# esp_slave.net
KiCad netlist of a schematic drawn in Altium Designer
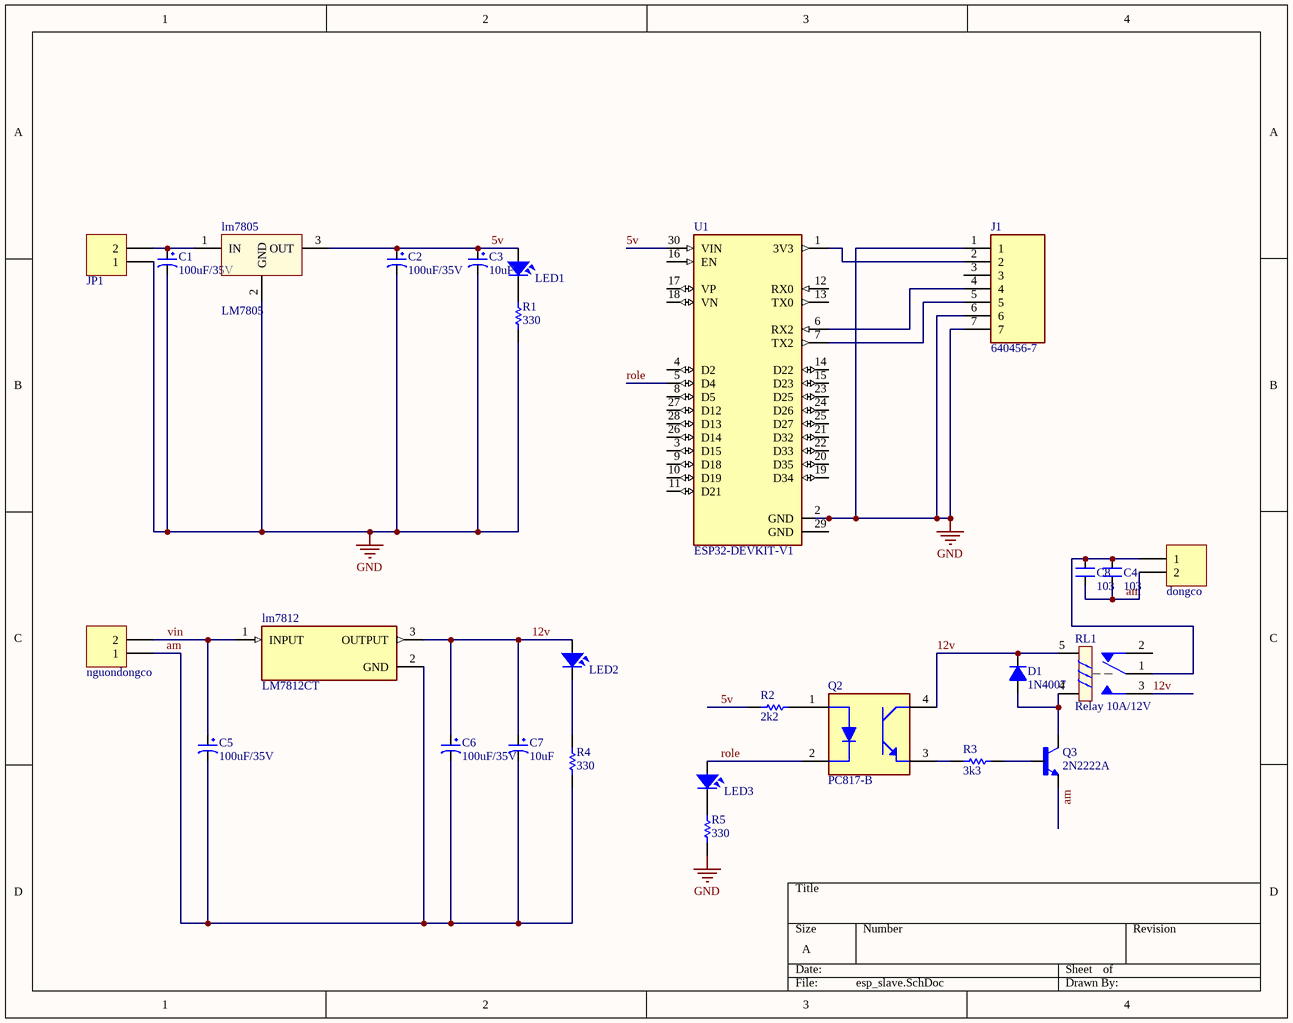
[diagram p0: esp_slave.SchDoc]

(export (version "E")
  (design (tool "Eeschema 10.0.6"))
  (components
    (comp (ref "C1")
      (value "100uF/35V")
      (footprint "CP1.5/3.4")
      (description "Cap 100uF/35V - 470uF/16V")
      (libsource (lib "syhaunguyen") (part "CP3"))
    )
    (comp (ref "C2")
      (value "100uF/35V")
      (footprint "CP1.5/3.4")
      (description "Cap 100uF/35V - 470uF/16V")
      (libsource (lib "syhaunguyen") (part "CP3"))
    )
    (comp (ref "C3")
      (value "10uF")
      (footprint "CP1/2")
      (description "Cap P  0,1uF < 22uF , 16 - 50V")
      (libsource (lib "syhaunguyen") (part "CP1"))
    )
    (comp (ref "C4")
      (value "103")
      (footprint "CN1.5")
      (description "Cap np 682pF => 104pF")
      (libsource (lib "syhaunguyen") (part "CN1.5"))
    )
    (comp (ref "C5")
      (value "100uF/35V")
      (footprint "CP1.5/3.4")
      (description "Cap 100uF/35V - 470uF/16V")
      (libsource (lib "syhaunguyen") (part "CP3"))
    )
    (comp (ref "C6")
      (value "100uF/35V")
      (footprint "CP1.5/3.4")
      (description "Cap 100uF/35V - 470uF/16V")
      (libsource (lib "syhaunguyen") (part "CP3"))
    )
    (comp (ref "C7")
      (value "10uF")
      (footprint "CP1/2")
      (description "Cap P  0,1uF < 22uF , 16 - 50V")
      (libsource (lib "syhaunguyen") (part "CP1"))
    )
    (comp (ref "C8")
      (value "103")
      (footprint "CN1.5")
      (description "Cap np 682pF => 104pF")
      (libsource (lib "syhaunguyen") (part "CN1.5"))
    )
    (comp (ref "D1")
      (value "1N4007")
      (footprint "D1A")
      (description "Diode 1A")
      (libsource (lib "syhaunguyen") (part "D1A"))
    )
    (comp (ref "dongco")
      (value "Header 2_1")
      (footprint "HED2")
      (description "Header, 2-Pin")
      (fields (field (name "MANUFACTURER") "Generic Components"))
      (libsource (lib "syhaunguyen") (part "Header 2_1"))
    )
    (comp (ref "J1")
      (value "640456-7")
      (footprint "TE_640456-7")
      (description "Header Friction Lock MTA-100 7 250 VAC Polyester Tin Copper Alloy Tin ¦ TE Connectivity 640456-7")
      (fields (field (name "MF") "TE Connectivity"))
      (libsource (lib "640456-7") (part "640456-7"))
    )
    (comp (ref "JP1")
      (value "Header 2_1")
      (footprint "HED2")
      (description "Header, 2-Pin")
      (fields (field (name "MANUFACTURER") "Generic Components"))
      (libsource (lib "") (part "Header 2_1_1"))
    )
    (comp (ref "LED1")
      (value "LED")
      (footprint "LED-3")
      (description "LED Single colour Green and Red")
      (libsource (lib "syhaunguyen") (part "LED"))
    )
    (comp (ref "LED2")
      (value "LED")
      (footprint "LED-3")
      (description "LED Single colour Green and Red")
      (libsource (lib "syhaunguyen") (part "LED"))
    )
    (comp (ref "LED3")
      (value "LED")
      (footprint "LED-3")
      (description "LED Single colour Green and Red")
      (libsource (lib "syhaunguyen") (part "LED"))
    )
    (comp (ref "lm7805")
      (value "LM7805")
      (footprint "QTO-220")
      (description "On ap +, from + 5 to + 24VDC")
      (libsource (lib "syhaunguyen") (part "LM78xx"))
    )
    (comp (ref "lm7812")
      (value "LM7812CT")
      (footprint "TO253P1057X470X2040-3")
      (description "Linear Voltage Regulator IC Positive Fixed 1 Output 1A TO-220-3")
      (fields (field (name "MF") "ON Semiconductor"))
      (libsource (lib "LM7812CT") (part "LM7812CT"))
    )
    (comp (ref "nguondongco")
      (value "Header 2_1")
      (footprint "HED2")
      (description "Header, 2-Pin")
      (fields (field (name "MANUFACTURER") "Generic Components"))
      (libsource (lib "") (part "Header 2_1_1"))
    )
    (comp (ref "Q2")
      (value "PC817-B")
      (footprint "DIP762W50P254L650H455Q4B")
      (description "Phototransistors 4-DIP (0.300, 7.62mm)")
      (fields (field (name "MF") "American Bright"))
      (libsource (lib "PC817-B") (part "PC817-B"))
    )
    (comp (ref "Q3")
      (value "2N2222A")
      (footprint "TO92254P470H750-3")
      (description "BJT, TO-92, 40V, 600mA, NPN, 0.625W, 150Â°C")
      (fields (field (name "MF") "Diotec Semiconductor"))
      (libsource (lib "2N2222A") (part "2N2222A"))
    )
    (comp (ref "R1")
      (value "330")
      (footprint "R1/4W")
      (description "Resistor")
      (fields
        (field (name "MANUFACTURER") "Generic Components")
        (field (name "Comment") "Res1")
        (field (name "PUBLISHER") "Altium Hobart Technology Centre")
      )
      (libsource (lib "syhaunguyen") (part "Res1_4"))
    )
    (comp (ref "R2")
      (value "2k2")
      (footprint "R1/4W")
      (description "Resistor")
      (fields
        (field (name "MANUFACTURER") "Generic Components")
        (field (name "Comment") "Res1")
        (field (name "PUBLISHER") "Altium Hobart Technology Centre")
      )
      (libsource (lib "syhaunguyen") (part "Res1_4"))
    )
    (comp (ref "R3")
      (value "3k3")
      (footprint "R1/4W")
      (description "Resistor")
      (fields
        (field (name "MANUFACTURER") "Generic Components")
        (field (name "Comment") "Res1")
        (field (name "PUBLISHER") "Altium Hobart Technology Centre")
      )
      (libsource (lib "syhaunguyen") (part "Res1_4"))
    )
    (comp (ref "R4")
      (value "330")
      (footprint "R1/4W")
      (description "Resistor")
      (fields
        (field (name "MANUFACTURER") "Generic Components")
        (field (name "Comment") "Res1")
        (field (name "PUBLISHER") "Altium Hobart Technology Centre")
      )
      (libsource (lib "syhaunguyen") (part "Res1_4"))
    )
    (comp (ref "R5")
      (value "330")
      (footprint "R1/4W")
      (description "Resistor")
      (fields
        (field (name "MANUFACTURER") "Generic Components")
        (field (name "Comment") "Res1")
        (field (name "PUBLISHER") "Altium Hobart Technology Centre")
      )
      (libsource (lib "syhaunguyen") (part "Res1_4"))
    )
    (comp (ref "RL1")
      (value "Relay 10A/12V")
      (footprint "RL_SPDT_10A")
      (description "Relay SPDT,10A - 12VDC 5 Pin")
      (libsource (lib "syhaunguyen") (part "Relay 1"))
    )
    (comp (ref "U1")
      (value "ESP32-DEVKIT-V1")
      (footprint "MODULE_ESP32_DEVKIT_V1")
      (fields (field (name "MF") "Do it"))
      (libsource (lib "ESP32-DEVKIT-V1") (part "ESP32-DEVKIT-V1"))
    )
  )
  (nets
    (net (code "1") (name "/5v") (class "Default")
      (node (ref "C2") (pin "1") (pinfunction "1_1") (pintype "passive"))
      (node (ref "C3") (pin "1") (pinfunction "1_1") (pintype "passive"))
      (node (ref "LED1") (pin "1") (pinfunction "1_1") (pintype "passive"))
      (node (ref "R2") (pin "1") (pinfunction "1_1") (pintype "passive"))
      (node (ref "U1") (pin "30") (pinfunction "VIN_30") (pintype "input"))
      (node (ref "lm7805") (pin "3") (pinfunction "OUT_3") (pintype "passive"))
    )
    (net (code "2") (name "/12v") (class "Default")
      (node (ref "C6") (pin "1") (pinfunction "1_1") (pintype "passive"))
      (node (ref "C7") (pin "1") (pinfunction "1_1") (pintype "passive"))
      (node (ref "D1") (pin "2") (pinfunction "K_2") (pintype "passive"))
      (node (ref "LED2") (pin "1") (pinfunction "1_1") (pintype "passive"))
      (node (ref "Q2") (pin "4") (pinfunction "COLLECTOR_4") (pintype "passive"))
      (node (ref "RL1") (pin "3") (pinfunction "3_3") (pintype "passive"))
      (node (ref "RL1") (pin "5") (pinfunction "5_5") (pintype "passive"))
      (node (ref "lm7812") (pin "3") (pinfunction "OUTPUT_3") (pintype "output"))
    )
    (net (code "3") (name "/am") (class "Default")
      (node (ref "C4") (pin "1") (pinfunction "1_1") (pintype "passive"))
      (node (ref "C5") (pin "2") (pinfunction "2_2") (pintype "passive"))
      (node (ref "C6") (pin "2") (pinfunction "2_2") (pintype "passive"))
      (node (ref "C7") (pin "2") (pinfunction "2_2") (pintype "passive"))
      (node (ref "C8") (pin "1") (pinfunction "1_1") (pintype "passive"))
      (node (ref "Q3") (pin "1") (pinfunction "E_1") (pintype "passive"))
      (node (ref "R4") (pin "2") (pinfunction "2_2") (pintype "passive"))
      (node (ref "dongco") (pin "2") (pinfunction "2_2") (pintype "passive"))
      (node (ref "lm7812") (pin "2") (pinfunction "GND_2") (pintype "power_in"))
      (node (ref "nguondongco") (pin "1") (pinfunction "1_1") (pintype "passive"))
    )
    (net (code "4") (name "/role") (class "Default")
      (node (ref "LED3") (pin "1") (pinfunction "1_1") (pintype "passive"))
      (node (ref "Q2") (pin "2") (pinfunction "CATHODE_2") (pintype "passive"))
      (node (ref "U1") (pin "5") (pinfunction "D4_5") (pintype "bidirectional"))
    )
    (net (code "5") (name "/vin") (class "Default")
      (node (ref "C5") (pin "1") (pinfunction "1_1") (pintype "passive"))
      (node (ref "lm7812") (pin "1") (pinfunction "INPUT_1") (pintype "input"))
      (node (ref "nguondongco") (pin "2") (pinfunction "2_2") (pintype "passive"))
    )
    (net (code "6") (name "GND") (class "Default")
      (node (ref "C1") (pin "2") (pinfunction "2_2") (pintype "passive"))
      (node (ref "C2") (pin "2") (pinfunction "2_2") (pintype "passive"))
      (node (ref "C3") (pin "2") (pinfunction "2_2") (pintype "passive"))
      (node (ref "J1") (pin "1") (pinfunction "1_1") (pintype "passive"))
      (node (ref "J1") (pin "6") (pinfunction "6_6") (pintype "passive"))
      (node (ref "J1") (pin "7") (pinfunction "7_7") (pintype "passive"))
      (node (ref "JP1") (pin "1") (pinfunction "1_1") (pintype "passive"))
      (node (ref "R1") (pin "2") (pinfunction "2_2") (pintype "passive"))
      (node (ref "R5") (pin "2") (pinfunction "2_2") (pintype "passive"))
      (node (ref "U1") (pin "2") (pinfunction "GND_2") (pintype "power_in"))
      (node (ref "lm7805") (pin "2") (pinfunction "GND_2") (pintype "passive"))
    )
    (net (code "7") (name "Net-(C4-Pad2)") (class "Default")
      (node (ref "C4") (pin "2") (pinfunction "2_2") (pintype "passive"))
      (node (ref "C8") (pin "2") (pinfunction "2_2") (pintype "passive"))
      (node (ref "RL1") (pin "1") (pinfunction "1_1") (pintype "passive"))
      (node (ref "dongco") (pin "1") (pinfunction "1_1") (pintype "passive"))
    )
    (net (code "8") (name "Net-(D1-A)") (class "Default")
      (node (ref "D1") (pin "1") (pinfunction "A_1") (pintype "passive"))
      (node (ref "Q3") (pin "3") (pinfunction "C_3") (pintype "passive"))
      (node (ref "RL1") (pin "4") (pinfunction "4_4") (pintype "passive"))
    )
    (net (code "9") (name "Net-(LED1-Pad2)") (class "Default")
      (node (ref "LED1") (pin "2") (pinfunction "2_2") (pintype "passive"))
      (node (ref "R1") (pin "1") (pinfunction "1_1") (pintype "passive"))
    )
    (net (code "10") (name "Net-(LED2-Pad2)") (class "Default")
      (node (ref "LED2") (pin "2") (pinfunction "2_2") (pintype "passive"))
      (node (ref "R4") (pin "1") (pinfunction "1_1") (pintype "passive"))
    )
    (net (code "11") (name "Net-(LED3-Pad2)") (class "Default")
      (node (ref "LED3") (pin "2") (pinfunction "2_2") (pintype "passive"))
      (node (ref "R5") (pin "1") (pinfunction "1_1") (pintype "passive"))
    )
    (net (code "12") (name "Net-(Q2-ANODE)") (class "Default")
      (node (ref "Q2") (pin "1") (pinfunction "ANODE_1") (pintype "passive"))
      (node (ref "R2") (pin "2") (pinfunction "2_2") (pintype "passive"))
    )
    (net (code "13") (name "Net-(Q2-EMITTER)") (class "Default")
      (node (ref "Q2") (pin "3") (pinfunction "EMITTER_3") (pintype "passive"))
      (node (ref "R3") (pin "1") (pinfunction "1_1") (pintype "passive"))
    )
    (net (code "14") (name "Net-(Q3-B)") (class "Default")
      (node (ref "Q3") (pin "2") (pinfunction "B_2") (pintype "passive"))
      (node (ref "R3") (pin "2") (pinfunction "2_2") (pintype "passive"))
    )
    (net (code "15") (name "Net-(U1-3V3)") (class "Default")
      (node (ref "J1") (pin "2") (pinfunction "2_2") (pintype "passive"))
      (node (ref "U1") (pin "1") (pinfunction "3V3_1") (pintype "output"))
    )
    (net (code "16") (name "Net-(U1-RX2)") (class "Default")
      (node (ref "J1") (pin "4") (pinfunction "4_4") (pintype "passive"))
      (node (ref "U1") (pin "6") (pinfunction "RX2_6") (pintype "input"))
    )
    (net (code "17") (name "Net-(U1-TX2)") (class "Default")
      (node (ref "J1") (pin "5") (pinfunction "5_5") (pintype "passive"))
      (node (ref "U1") (pin "7") (pinfunction "TX2_7") (pintype "output"))
    )
    (net (code "18") (name "Net-(lm7805-IN)") (class "Default")
      (node (ref "C1") (pin "1") (pinfunction "1_1") (pintype "passive"))
      (node (ref "JP1") (pin "2") (pinfunction "2_2") (pintype "passive"))
      (node (ref "lm7805") (pin "1") (pinfunction "IN_1") (pintype "passive"))
    )
    (net (code "19") (name "unconnected-(J1-Pad3)") (class "Default")
      (node (ref "J1") (pin "3") (pinfunction "3_3") (pintype "passive"))
    )
    (net (code "20") (name "unconnected-(RL1-Pad2)") (class "Default")
      (node (ref "RL1") (pin "2") (pinfunction "2_2") (pintype "passive"))
    )
    (net (code "21") (name "unconnected-(U1-D2-Pad4)") (class "Default")
      (node (ref "U1") (pin "4") (pinfunction "D2_4") (pintype "bidirectional"))
    )
    (net (code "22") (name "unconnected-(U1-D5-Pad8)") (class "Default")
      (node (ref "U1") (pin "8") (pinfunction "D5_8") (pintype "bidirectional"))
    )
    (net (code "23") (name "unconnected-(U1-D12-Pad27)") (class "Default")
      (node (ref "U1") (pin "27") (pinfunction "D12_27") (pintype "bidirectional"))
    )
    (net (code "24") (name "unconnected-(U1-D13-Pad28)") (class "Default")
      (node (ref "U1") (pin "28") (pinfunction "D13_28") (pintype "bidirectional"))
    )
    (net (code "25") (name "unconnected-(U1-D14-Pad26)") (class "Default")
      (node (ref "U1") (pin "26") (pinfunction "D14_26") (pintype "bidirectional"))
    )
    (net (code "26") (name "unconnected-(U1-D15-Pad3)") (class "Default")
      (node (ref "U1") (pin "3") (pinfunction "D15_3") (pintype "bidirectional"))
    )
    (net (code "27") (name "unconnected-(U1-D18-Pad9)") (class "Default")
      (node (ref "U1") (pin "9") (pinfunction "D18_9") (pintype "bidirectional"))
    )
    (net (code "28") (name "unconnected-(U1-D19-Pad10)") (class "Default")
      (node (ref "U1") (pin "10") (pinfunction "D19_10") (pintype "bidirectional"))
    )
    (net (code "29") (name "unconnected-(U1-D21-Pad11)") (class "Default")
      (node (ref "U1") (pin "11") (pinfunction "D21_11") (pintype "bidirectional"))
    )
    (net (code "30") (name "unconnected-(U1-D22-Pad14)") (class "Default")
      (node (ref "U1") (pin "14") (pinfunction "D22_14") (pintype "bidirectional"))
    )
    (net (code "31") (name "unconnected-(U1-D23-Pad15)") (class "Default")
      (node (ref "U1") (pin "15") (pinfunction "D23_15") (pintype "bidirectional"))
    )
    (net (code "32") (name "unconnected-(U1-D25-Pad23)") (class "Default")
      (node (ref "U1") (pin "23") (pinfunction "D25_23") (pintype "bidirectional"))
    )
    (net (code "33") (name "unconnected-(U1-D26-Pad24)") (class "Default")
      (node (ref "U1") (pin "24") (pinfunction "D26_24") (pintype "bidirectional"))
    )
    (net (code "34") (name "unconnected-(U1-D27-Pad25)") (class "Default")
      (node (ref "U1") (pin "25") (pinfunction "D27_25") (pintype "bidirectional"))
    )
    (net (code "35") (name "unconnected-(U1-D32-Pad21)") (class "Default")
      (node (ref "U1") (pin "21") (pinfunction "D32_21") (pintype "bidirectional"))
    )
    (net (code "36") (name "unconnected-(U1-D33-Pad22)") (class "Default")
      (node (ref "U1") (pin "22") (pinfunction "D33_22") (pintype "bidirectional"))
    )
    (net (code "37") (name "unconnected-(U1-D34-Pad19)") (class "Default")
      (node (ref "U1") (pin "19") (pinfunction "D34_19") (pintype "bidirectional"))
    )
    (net (code "38") (name "unconnected-(U1-D35-Pad20)") (class "Default")
      (node (ref "U1") (pin "20") (pinfunction "D35_20") (pintype "bidirectional"))
    )
    (net (code "39") (name "unconnected-(U1-EN-Pad16)") (class "Default")
      (node (ref "U1") (pin "16") (pinfunction "EN_16") (pintype "input"))
    )
    (net (code "40") (name "unconnected-(U1-GND-Pad29)") (class "Default")
      (node (ref "U1") (pin "29") (pinfunction "GND_29") (pintype "power_in"))
    )
    (net (code "41") (name "unconnected-(U1-RX0-Pad12)") (class "Default")
      (node (ref "U1") (pin "12") (pinfunction "RX0_12") (pintype "input"))
    )
    (net (code "42") (name "unconnected-(U1-TX0-Pad13)") (class "Default")
      (node (ref "U1") (pin "13") (pinfunction "TX0_13") (pintype "output"))
    )
    (net (code "43") (name "unconnected-(U1-VN-Pad18)") (class "Default")
      (node (ref "U1") (pin "18") (pinfunction "VN_18") (pintype "bidirectional"))
    )
    (net (code "44") (name "unconnected-(U1-VP-Pad17)") (class "Default")
      (node (ref "U1") (pin "17") (pinfunction "VP_17") (pintype "bidirectional"))
    )
  )
)
